# power.net
KiCad netlist of a schematic drawn in Altium Designer
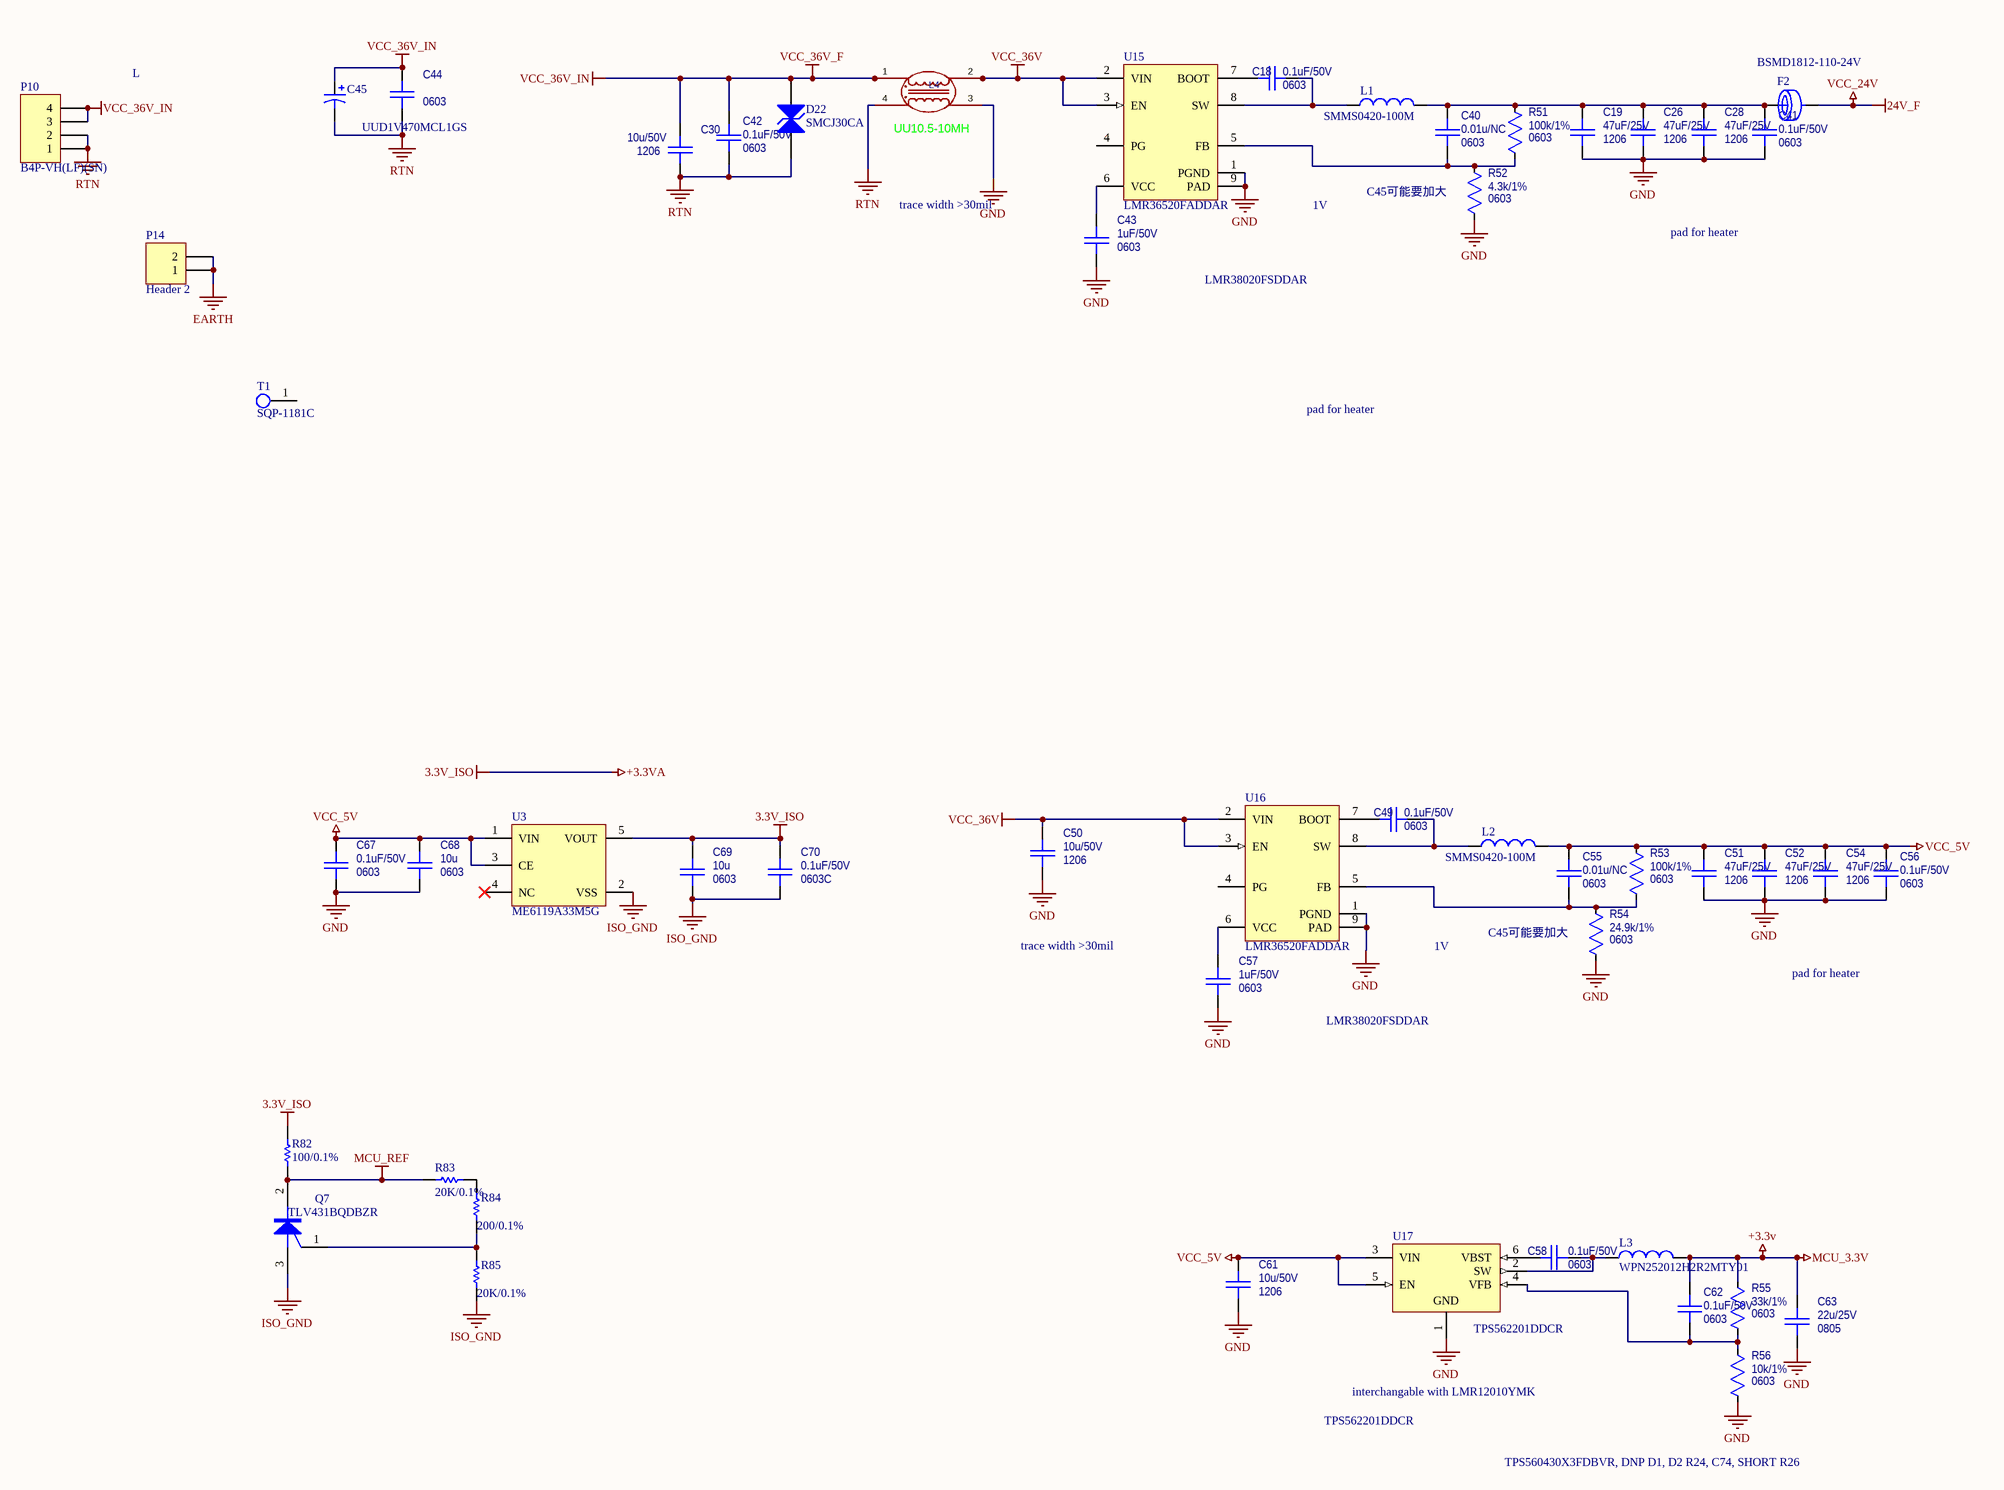
[diagram p0: power.SchDoc]

(export (version "E")
  (design (tool "Eeschema 10.0.6"))
  (components
    (comp (ref "C18")
      (value "0.1uF/50V")
      (footprint "0603C")
      (fields (field (name "PACKAGE") "0603"))
      (libsource (lib "Karl") (part "Capacitor_0603"))
    )
    (comp (ref "C19")
      (value "47uF/25V")
      (footprint "CAPC3216X156N_1206")
      (fields (field (name "PACKAGE") "1206"))
      (libsource (lib "Karl") (part "Capacitor_1206"))
    )
    (comp (ref "C26")
      (value "47uF/25V")
      (footprint "CAPC3216X156N_1206")
      (fields (field (name "PACKAGE") "1206"))
      (libsource (lib "Karl") (part "Capacitor_1206"))
    )
    (comp (ref "C28")
      (value "47uF/25V")
      (footprint "CAPC3216X156N_1206")
      (fields (field (name "PACKAGE") "1206"))
      (libsource (lib "Karl") (part "Capacitor_1206"))
    )
    (comp (ref "C30")
      (value "10u/50V")
      (footprint "CAPC3216X156N_1206")
      (fields (field (name "PACKAGE") "1206"))
      (libsource (lib "Karl") (part "Capacitor_1206"))
    )
    (comp (ref "C40")
      (value "0.01u/NC")
      (footprint "0603C")
      (fields (field (name "PACKAGE") "0603") (field (name "Comment") "0.01uF/50V"))
      (libsource (lib "Karl") (part "Capacitor_0603"))
    )
    (comp (ref "C41")
      (value "0.1uF/50V")
      (footprint "0603C")
      (fields (field (name "PACKAGE") "0603"))
      (libsource (lib "Karl") (part "Capacitor_0603"))
    )
    (comp (ref "C42")
      (value "0.1uF/50V")
      (footprint "0603C")
      (fields (field (name "PACKAGE") "0603"))
      (libsource (lib "Karl") (part "Capacitor_0603"))
    )
    (comp (ref "C43")
      (value "1uF/50V")
      (footprint "0603C")
      (fields (field (name "PACKAGE") "0603"))
      (libsource (lib "Karl") (part "Capacitor_0603"))
    )
    (comp (ref "C44")
      (value "10uF/16V")
      (footprint "0603c")
      (description "Capacitor, MLCC")
      (fields (field (name "PACKAGE") "0603"))
      (libsource (lib "Karl") (part "Capacitor_0603"))
    )
    (comp (ref "C45")
      (value "UUD1V470MCL1GS")
      (footprint "Φ10×10")
      (description "Polarized Capacitor (Radial)")
      (libsource (lib "Miscellaneous Devices") (part "Cap Pol1"))
    )
    (comp (ref "C49")
      (value "0.1uF/50V")
      (footprint "0603C")
      (fields (field (name "PACKAGE") "0603"))
      (libsource (lib "Karl") (part "Capacitor_0603"))
    )
    (comp (ref "C50")
      (value "10u/50V")
      (footprint "CAPC3216X156N_1206")
      (fields (field (name "PACKAGE") "1206"))
      (libsource (lib "Karl") (part "Capacitor_1206"))
    )
    (comp (ref "C51")
      (value "47uF/25V")
      (footprint "CAPC3216X156N_1206")
      (fields (field (name "PACKAGE") "1206"))
      (libsource (lib "Karl") (part "Capacitor_1206"))
    )
    (comp (ref "C52")
      (value "47uF/25V")
      (footprint "CAPC3216X156N_1206")
      (fields (field (name "PACKAGE") "1206"))
      (libsource (lib "Karl") (part "Capacitor_1206"))
    )
    (comp (ref "C54")
      (value "47uF/25V")
      (footprint "CAPC3216X156N_1206")
      (fields (field (name "PACKAGE") "1206"))
      (libsource (lib "Karl") (part "Capacitor_1206"))
    )
    (comp (ref "C55")
      (value "0.01u/NC")
      (footprint "0603C")
      (fields (field (name "PACKAGE") "0603") (field (name "Comment") "0.01uF/50V"))
      (libsource (lib "Karl") (part "Capacitor_0603"))
    )
    (comp (ref "C56")
      (value "0.1uF/50V")
      (footprint "0603C")
      (fields (field (name "PACKAGE") "0603"))
      (libsource (lib "Karl") (part "Capacitor_0603"))
    )
    (comp (ref "C57")
      (value "1uF/50V")
      (footprint "0603C")
      (fields (field (name "PACKAGE") "0603"))
      (libsource (lib "Karl") (part "Capacitor_0603"))
    )
    (comp (ref "C58")
      (value "0.1uF/50V")
      (footprint "0603C")
      (fields (field (name "PACKAGE") "0603"))
      (libsource (lib "Karl") (part "Capacitor_0603"))
    )
    (comp (ref "C61")
      (value "10u/50V")
      (footprint "CAPC3216X156N_1206")
      (fields (field (name "PACKAGE") "1206"))
      (libsource (lib "Karl") (part "Capacitor_0805"))
    )
    (comp (ref "C62")
      (value "0.1uF/50V")
      (footprint "0603C")
      (fields (field (name "PACKAGE") "0603"))
      (libsource (lib "Karl") (part "Capacitor_0603"))
    )
    (comp (ref "C63")
      (value "22u/25V")
      (footprint "CAPC2012X127N_0805")
      (fields (field (name "PACKAGE") "0805"))
      (libsource (lib "Karl") (part "Capacitor_0805"))
    )
    (comp (ref "C67")
      (value "0.1uF/50V")
      (footprint "0603C")
      (description "Capacitor, MLCC")
      (fields (field (name "PACKAGE") "0603"))
      (libsource (lib "Karl") (part "Capacitor_0603"))
    )
    (comp (ref "C68")
      (value "10u")
      (footprint "0603c")
      (description "Capacitor, MLCC")
      (fields (field (name "PACKAGE") "0603") (field (name "Comment") "10uF/16V"))
      (libsource (lib "Karl") (part "Capacitor_0603"))
    )
    (comp (ref "C69")
      (value "10u")
      (footprint "0603c")
      (description "Capacitor, MLCC")
      (fields (field (name "PACKAGE") "0603") (field (name "Comment") "10uF/16V"))
      (libsource (lib "Karl") (part "Capacitor_0603"))
    )
    (comp (ref "C70")
      (value "0.1uF/50V")
      (footprint "0603C")
      (description "Capacitor, MLCC")
      (fields (field (name "PACKAGE") "0603C"))
      (libsource (lib "Karl") (part "Capacitor_0402"))
    )
    (comp (ref "D22")
      (value "SMCJ30CA")
      (footprint "SMC")
      (description "Transient Voltage Suppression Diode, 400 W, 33 V, -65 to 150 degC, 2-Pin SMD, RoHS, Tape and Reel")
      (fields (field (name "MANUFACTURER") "Littelfuse"))
      (libsource (lib "Bogen") (part "SMAJ12CA"))
    )
    (comp (ref "F2")
      (value "BSMD1812-110-24V")
      (footprint "1812-F")
      (description "Ferrite Bead Chip")
      (libsource (lib "Karl") (part "FBC0603"))
    )
    (comp (ref "L1")
      (value "SMMS0420-100M")
      (footprint "IND-SMD_L4.5-W4.5_SMMS0420:IND-SMD_L4.5-W4.5_SMMS0420")
      (description "Metal alloy Power Inductor, 10 uH, ±20%, 1210 (3225)")
      (libsource (lib "Bogen") (part "1276AS-H-100M=P2"))
    )
    (comp (ref "L2")
      (value "SMMS0420-100M")
      (footprint "IND-SMD_L4.5-W4.5_SMMS0420:IND-SMD_L4.5-W4.5_SMMS0420")
      (description "Metal alloy Power Inductor, 10 uH, ±20%, 1210 (3225)")
      (libsource (lib "Bogen") (part "1276AS-H-100M=P2"))
    )
    (comp (ref "L3")
      (value "WPN252012H2R2MTY01")
      (footprint "PULS-BDCD00252012_V")
      (libsource (lib "Bogen") (part "BDCD002520122R2MS1"))
    )
    (comp (ref "L4")
      (value "UU10.5-10MH")
      (footprint "FILTER-TH_4P-L19.5-W18.0-P10.00-D0.7-S13.00:FILTER-TH_4P-L19.5-W18.0-P10.00-D0.7-S13.00")
      (libsource (lib "altium-import") (part "root_0_UU10.5-10MH_"))
    )
    (comp (ref "P10")
      (value "B4P-VH(LF)(SN)")
      (footprint "CONN-TH_4P-P3.96_HX-VH3.96-4P-ZZ")
      (description "Header, 4-Pin")
      (libsource (lib "Miscellaneous Connectors") (part "Header 4"))
    )
    (comp (ref "P14")
      (value "Header 2")
      (footprint "插片端子4.8*0.8mm")
      (description "Header, 2-Pin")
      (libsource (lib "Miscellaneous Connectors") (part "Header 2"))
    )
    (comp (ref "Q7")
      (value "TLV431BQDBZR")
      (footprint "SOT23-3")
      (description "Programmable Unijunction Transistor")
      (libsource (lib "Miscellaneous Devices") (part "PUT"))
    )
    (comp (ref "R51")
      (value "100k/1%")
      (footprint "0603R")
      (fields (field (name "PACKAGE") "0603"))
      (libsource (lib "Karl") (part "Resistor_0603"))
    )
    (comp (ref "R52")
      (value "4.3k/1%")
      (footprint "0603R")
      (fields (field (name "PACKAGE") "0603"))
      (libsource (lib "Karl") (part "Resistor_0603"))
    )
    (comp (ref "R53")
      (value "100k/1%")
      (footprint "0603R")
      (fields (field (name "PACKAGE") "0603"))
      (libsource (lib "Karl") (part "Resistor_0603"))
    )
    (comp (ref "R54")
      (value "24.9k/1%")
      (footprint "0603R")
      (fields (field (name "PACKAGE") "0603"))
      (libsource (lib "Karl") (part "Resistor_0603"))
    )
    (comp (ref "R55")
      (value "33k/1%")
      (footprint "0603R")
      (fields (field (name "PACKAGE") "0603"))
      (libsource (lib "Karl") (part "Resistor_0603"))
    )
    (comp (ref "R56")
      (value "10k/1%")
      (footprint "0603R")
      (fields (field (name "PACKAGE") "0603"))
      (libsource (lib "Karl") (part "Resistor_0603"))
    )
    (comp (ref "R82")
      (value "100/0.1%")
      (footprint "0603R")
      (description "Resistor")
      (libsource (lib "Miscellaneous Devices") (part "Res1"))
    )
    (comp (ref "R83")
      (value "20K/0.1%")
      (footprint "0603R")
      (description "Resistor")
      (libsource (lib "Miscellaneous Devices") (part "Res1"))
    )
    (comp (ref "R84")
      (value "200/0.1%")
      (footprint "0603R")
      (description "Resistor")
      (libsource (lib "Miscellaneous Devices") (part "Res1"))
    )
    (comp (ref "R85")
      (value "20K/0.1%")
      (footprint "0603R")
      (description "Resistor")
      (libsource (lib "Miscellaneous Devices") (part "Res1"))
    )
    (comp (ref "T1")
      (value "SQP-1181C")
      (footprint "SQP-1181C")
      (libsource (lib "Schlib_20110825") (part "TP"))
    )
    (comp (ref "U3")
      (value "ME6119A33M5G")
      (footprint "MCRN-SOT23-5_V")
      (libsource (lib "Bogen") (part "ME6119C50M5G"))
    )
    (comp (ref "U15")
      (value "LMR36520FADDAR")
      (footprint "DDA0008A_M")
      (libsource (lib "Bogen") (part "LMR36520FADDAR"))
    )
    (comp (ref "U16")
      (value "LMR36520FADDAR")
      (footprint "DDA0008A_M")
      (libsource (lib "Bogen") (part "LMR36520FADDAR"))
    )
    (comp (ref "U17")
      (value "TPS562201DDCR")
      (footprint "DDC0006A_L")
      (libsource (lib "Bogen") (part "TPS562201DDCR"))
    )
  )
  (nets
    (net (code "1") (name "+3.3VA") (class "Default")
      (node (ref "C69") (pin "1") (pinfunction "1_1") (pintype "passive"))
      (node (ref "C70") (pin "1") (pinfunction "1_1") (pintype "passive"))
      (node (ref "R82") (pin "1") (pinfunction "1_1") (pintype "passive"))
      (node (ref "U3") (pin "5") (pinfunction "VOUT_5") (pintype "passive"))
    )
    (net (code "2") (name "+3.3v") (class "Default")
      (node (ref "C62") (pin "1") (pinfunction "1_1") (pintype "passive"))
      (node (ref "C63") (pin "1") (pinfunction "1_1") (pintype "passive"))
      (node (ref "L3") (pin "2") (pinfunction "2_2") (pintype "passive"))
      (node (ref "R55") (pin "2") (pinfunction "2_2") (pintype "passive"))
    )
    (net (code "3") (name "24V_F") (class "Default")
      (node (ref "F2") (pin "2") (pinfunction "2_2") (pintype "passive"))
    )
    (net (code "4") (name "EARTH") (class "Default")
      (node (ref "P14") (pin "1") (pinfunction "1_1") (pintype "passive"))
      (node (ref "P14") (pin "2") (pinfunction "2_2") (pintype "passive"))
    )
    (net (code "5") (name "GND") (class "Default")
      (node (ref "C19") (pin "2") (pinfunction "2_2") (pintype "passive"))
      (node (ref "C26") (pin "2") (pinfunction "2_2") (pintype "passive"))
      (node (ref "C28") (pin "2") (pinfunction "2_2") (pintype "passive"))
      (node (ref "C41") (pin "2") (pinfunction "2_2") (pintype "passive"))
      (node (ref "C43") (pin "2") (pinfunction "2_2") (pintype "passive"))
      (node (ref "C50") (pin "2") (pinfunction "2_2") (pintype "passive"))
      (node (ref "C51") (pin "2") (pinfunction "2_2") (pintype "passive"))
      (node (ref "C52") (pin "2") (pinfunction "2_2") (pintype "passive"))
      (node (ref "C54") (pin "2") (pinfunction "2_2") (pintype "passive"))
      (node (ref "C56") (pin "2") (pinfunction "2_2") (pintype "passive"))
      (node (ref "C57") (pin "2") (pinfunction "2_2") (pintype "passive"))
      (node (ref "C61") (pin "2") (pinfunction "2_2") (pintype "passive"))
      (node (ref "C63") (pin "2") (pinfunction "2_2") (pintype "passive"))
      (node (ref "C67") (pin "2") (pinfunction "2_2") (pintype "passive"))
      (node (ref "C68") (pin "2") (pinfunction "2_2") (pintype "passive"))
      (node (ref "L4") (pin "3") (pinfunction "3_3") (pintype "passive"))
      (node (ref "R52") (pin "1") (pinfunction "1_1") (pintype "passive"))
      (node (ref "R54") (pin "1") (pinfunction "1_1") (pintype "passive"))
      (node (ref "R56") (pin "1") (pinfunction "1_1") (pintype "passive"))
      (node (ref "U15") (pin "1") (pinfunction "PGND_1") (pintype "passive"))
      (node (ref "U15") (pin "9") (pinfunction "PAD_9") (pintype "passive"))
      (node (ref "U16") (pin "1") (pinfunction "PGND_1") (pintype "passive"))
      (node (ref "U16") (pin "9") (pinfunction "PAD_9") (pintype "passive"))
      (node (ref "U17") (pin "1") (pinfunction "GND_1") (pintype "power_in"))
    )
    (net (code "6") (name "ISO_GND") (class "Default")
      (node (ref "C69") (pin "2") (pinfunction "2_2") (pintype "passive"))
      (node (ref "C70") (pin "2") (pinfunction "2_2") (pintype "passive"))
      (node (ref "Q7") (pin "3") (pinfunction "A_3") (pintype "passive"))
      (node (ref "R85") (pin "2") (pinfunction "2_2") (pintype "passive"))
      (node (ref "U3") (pin "2") (pinfunction "VSS_2") (pintype "passive"))
    )
    (net (code "7") (name "MCU_REF") (class "Default")
      (node (ref "Q7") (pin "2") (pinfunction "K_2") (pintype "passive"))
      (node (ref "R82") (pin "2") (pinfunction "2_2") (pintype "passive"))
      (node (ref "R83") (pin "1") (pinfunction "1_1") (pintype "passive"))
    )
    (net (code "8") (name "Net-(C19-Pad1)") (class "Default")
      (node (ref "C19") (pin "1") (pinfunction "1_1") (pintype "passive"))
      (node (ref "C26") (pin "1") (pinfunction "1_1") (pintype "passive"))
      (node (ref "C28") (pin "1") (pinfunction "1_1") (pintype "passive"))
      (node (ref "C40") (pin "1") (pinfunction "1_1") (pintype "passive"))
      (node (ref "C41") (pin "1") (pinfunction "1_1") (pintype "passive"))
      (node (ref "F2") (pin "1") (pinfunction "1_1") (pintype "passive"))
      (node (ref "L1") (pin "2") (pinfunction "2_2") (pintype "passive"))
      (node (ref "R51") (pin "2") (pinfunction "2_2") (pintype "passive"))
    )
    (net (code "9") (name "Net-(Q7-G)") (class "Default")
      (node (ref "Q7") (pin "1") (pinfunction "G_1") (pintype "passive"))
      (node (ref "R84") (pin "2") (pinfunction "2_2") (pintype "passive"))
      (node (ref "R85") (pin "1") (pinfunction "1_1") (pintype "passive"))
    )
    (net (code "10") (name "Net-(R83-Pad2)") (class "Default")
      (node (ref "R83") (pin "2") (pinfunction "2_2") (pintype "passive"))
      (node (ref "R84") (pin "1") (pinfunction "1_1") (pintype "passive"))
    )
    (net (code "11") (name "Net-(U15-BOOT)") (class "Default")
      (node (ref "C18") (pin "1") (pinfunction "1_1") (pintype "passive"))
      (node (ref "U15") (pin "7") (pinfunction "BOOT_7") (pintype "passive"))
    )
    (net (code "12") (name "Net-(U15-FB)") (class "Default")
      (node (ref "C40") (pin "2") (pinfunction "2_2") (pintype "passive"))
      (node (ref "R51") (pin "1") (pinfunction "1_1") (pintype "passive"))
      (node (ref "R52") (pin "2") (pinfunction "2_2") (pintype "passive"))
      (node (ref "U15") (pin "5") (pinfunction "FB_5") (pintype "passive"))
    )
    (net (code "13") (name "Net-(U15-SW)") (class "Default")
      (node (ref "C18") (pin "2") (pinfunction "2_2") (pintype "passive"))
      (node (ref "L1") (pin "1") (pinfunction "1_1") (pintype "passive"))
      (node (ref "U15") (pin "8") (pinfunction "SW_8") (pintype "passive"))
    )
    (net (code "14") (name "Net-(U15-VCC)") (class "Default")
      (node (ref "C43") (pin "1") (pinfunction "1_1") (pintype "passive"))
      (node (ref "U15") (pin "6") (pinfunction "VCC_6") (pintype "passive"))
    )
    (net (code "15") (name "Net-(U16-BOOT)") (class "Default")
      (node (ref "C49") (pin "1") (pinfunction "1_1") (pintype "passive"))
      (node (ref "U16") (pin "7") (pinfunction "BOOT_7") (pintype "passive"))
    )
    (net (code "16") (name "Net-(U16-FB)") (class "Default")
      (node (ref "C55") (pin "2") (pinfunction "2_2") (pintype "passive"))
      (node (ref "R53") (pin "1") (pinfunction "1_1") (pintype "passive"))
      (node (ref "R54") (pin "2") (pinfunction "2_2") (pintype "passive"))
      (node (ref "U16") (pin "5") (pinfunction "FB_5") (pintype "passive"))
    )
    (net (code "17") (name "Net-(U16-SW)") (class "Default")
      (node (ref "C49") (pin "2") (pinfunction "2_2") (pintype "passive"))
      (node (ref "L2") (pin "1") (pinfunction "1_1") (pintype "passive"))
      (node (ref "U16") (pin "8") (pinfunction "SW_8") (pintype "passive"))
    )
    (net (code "18") (name "Net-(U16-VCC)") (class "Default")
      (node (ref "C57") (pin "1") (pinfunction "1_1") (pintype "passive"))
      (node (ref "U16") (pin "6") (pinfunction "VCC_6") (pintype "passive"))
    )
    (net (code "19") (name "Net-(U17-SW)") (class "Default")
      (node (ref "C58") (pin "2") (pinfunction "2_2") (pintype "passive"))
      (node (ref "L3") (pin "1") (pinfunction "1_1") (pintype "passive"))
      (node (ref "U17") (pin "2") (pinfunction "SW_2") (pintype "output"))
    )
    (net (code "20") (name "Net-(U17-VBST)") (class "Default")
      (node (ref "C58") (pin "1") (pinfunction "1_1") (pintype "passive"))
      (node (ref "U17") (pin "6") (pinfunction "VBST_6") (pintype "input"))
    )
    (net (code "21") (name "Net-(U17-VFB)") (class "Default")
      (node (ref "C62") (pin "2") (pinfunction "2_2") (pintype "passive"))
      (node (ref "R55") (pin "1") (pinfunction "1_1") (pintype "passive"))
      (node (ref "R56") (pin "2") (pinfunction "2_2") (pintype "passive"))
      (node (ref "U17") (pin "4") (pinfunction "VFB_4") (pintype "input"))
    )
    (net (code "22") (name "RTN") (class "Default")
      (node (ref "C30") (pin "2") (pinfunction "2_2") (pintype "passive"))
      (node (ref "C42") (pin "2") (pinfunction "2_2") (pintype "passive"))
      (node (ref "C44") (pin "2") (pinfunction "2_2") (pintype "passive"))
      (node (ref "C45") (pin "2") (pinfunction "2_2") (pintype "passive"))
      (node (ref "D22") (pin "1") (pinfunction "A_1") (pintype "passive"))
      (node (ref "L4") (pin "4") (pinfunction "4_4") (pintype "passive"))
      (node (ref "P10") (pin "1") (pinfunction "1_1") (pintype "passive"))
      (node (ref "P10") (pin "2") (pinfunction "2_2") (pintype "passive"))
    )
    (net (code "23") (name "VCC_5V") (class "Default")
      (node (ref "C51") (pin "1") (pinfunction "1_1") (pintype "passive"))
      (node (ref "C52") (pin "1") (pinfunction "1_1") (pintype "passive"))
      (node (ref "C54") (pin "1") (pinfunction "1_1") (pintype "passive"))
      (node (ref "C55") (pin "1") (pinfunction "1_1") (pintype "passive"))
      (node (ref "C56") (pin "1") (pinfunction "1_1") (pintype "passive"))
      (node (ref "C61") (pin "1") (pinfunction "1_1") (pintype "passive"))
      (node (ref "C67") (pin "1") (pinfunction "1_1") (pintype "passive"))
      (node (ref "C68") (pin "1") (pinfunction "1_1") (pintype "passive"))
      (node (ref "L2") (pin "2") (pinfunction "2_2") (pintype "passive"))
      (node (ref "R53") (pin "2") (pinfunction "2_2") (pintype "passive"))
      (node (ref "U17") (pin "3") (pinfunction "VIN_3") (pintype "power_in"))
      (node (ref "U17") (pin "5") (pinfunction "EN_5") (pintype "input"))
      (node (ref "U3") (pin "1") (pinfunction "VIN_1") (pintype "passive"))
      (node (ref "U3") (pin "3") (pinfunction "CE_3") (pintype "passive"))
    )
    (net (code "24") (name "VCC_36V") (class "Default")
      (node (ref "C50") (pin "1") (pinfunction "1_1") (pintype "passive"))
      (node (ref "L4") (pin "2") (pinfunction "2_2") (pintype "passive"))
      (node (ref "U15") (pin "2") (pinfunction "VIN_2") (pintype "passive"))
      (node (ref "U15") (pin "3") (pinfunction "EN_3") (pintype "input"))
      (node (ref "U16") (pin "2") (pinfunction "VIN_2") (pintype "passive"))
      (node (ref "U16") (pin "3") (pinfunction "EN_3") (pintype "input"))
    )
    (net (code "25") (name "VCC_36V_F") (class "Default")
      (node (ref "C30") (pin "1") (pinfunction "1_1") (pintype "passive"))
      (node (ref "C42") (pin "1") (pinfunction "1_1") (pintype "passive"))
      (node (ref "C44") (pin "1") (pinfunction "1_1") (pintype "passive"))
      (node (ref "C45") (pin "1") (pinfunction "1_1") (pintype "passive"))
      (node (ref "D22") (pin "2") (pinfunction "A_2") (pintype "passive"))
      (node (ref "L4") (pin "1") (pinfunction "1_1") (pintype "passive"))
      (node (ref "P10") (pin "3") (pinfunction "3_3") (pintype "passive"))
      (node (ref "P10") (pin "4") (pinfunction "4_4") (pintype "passive"))
    )
    (net (code "26") (name "unconnected-(T1-Pad1)") (class "Default")
      (node (ref "T1") (pin "1") (pintype "passive"))
    )
    (net (code "27") (name "unconnected-(U3-NC-Pad4)") (class "Default")
      (node (ref "U3") (pin "4") (pinfunction "NC_4") (pintype "passive+no_connect"))
    )
    (net (code "28") (name "unconnected-(U15-PG-Pad4)") (class "Default")
      (node (ref "U15") (pin "4") (pinfunction "PG_4") (pintype "passive"))
    )
    (net (code "29") (name "unconnected-(U16-PG-Pad4)") (class "Default")
      (node (ref "U16") (pin "4") (pinfunction "PG_4") (pintype "passive"))
    )
  )
)
